# Power_RevA.net
KiCad netlist of a schematic drawn in EAGLE
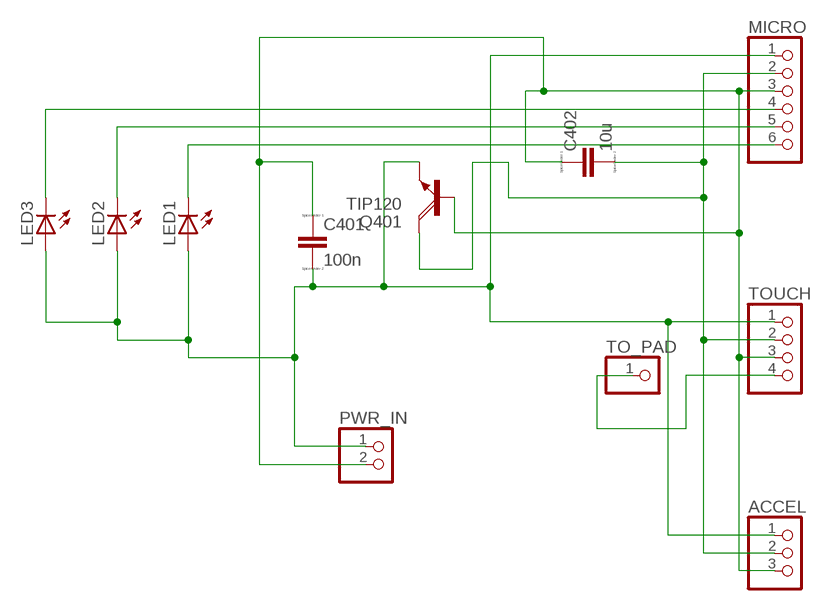
[diagram p0: schematic, sheet 1]

(export (version "E")
  (design (tool "Eeschema 10.0.6"))
  (components
    (comp (ref "ACCEL")
      (value "PINHD-1X3")
      (footprint "eagle-import:1X03")
      (libsource (lib "eagle-import") (part "PINHD-1X3"))
    )
    (comp (ref "C401")
      (value "100n")
      (footprint "eagle-import:C0603")
      (libsource (lib "eagle-import") (part "CC0603"))
    )
    (comp (ref "C402")
      (value "10u")
      (footprint "eagle-import:C0603")
      (libsource (lib "eagle-import") (part "CC0603"))
    )
    (comp (ref "LED1")
      (value "LEDP-LCC-4")
      (footprint "eagle-import:P-LCC-4")
      (libsource (lib "eagle-import") (part "LEDP-LCC-4"))
    )
    (comp (ref "LED2")
      (value "LEDP-LCC-4")
      (footprint "eagle-import:P-LCC-4")
      (libsource (lib "eagle-import") (part "LEDP-LCC-4"))
    )
    (comp (ref "LED3")
      (value "LEDP-LCC-4")
      (footprint "eagle-import:P-LCC-4")
      (libsource (lib "eagle-import") (part "LEDP-LCC-4"))
    )
    (comp (ref "MICRO")
      (value "PINHD-1X6")
      (footprint "eagle-import:1X06")
      (libsource (lib "eagle-import") (part "PINHD-1X6"))
    )
    (comp (ref "PWR_IN")
      (value "PINHD-1X2")
      (footprint "eagle-import:1X02")
      (libsource (lib "eagle-import") (part "PINHD-1X2"))
    )
    (comp (ref "Q401")
      (value "TIP120")
      (footprint "eagle-import:TO220AH")
      (libsource (lib "eagle-import") (part "TIP120"))
    )
    (comp (ref "TOUCH")
      (value "PINHD-1X4")
      (footprint "eagle-import:1X04")
      (libsource (lib "eagle-import") (part "PINHD-1X4"))
    )
    (comp (ref "TO_PAD")
      (value "PINHD-1X1")
      (footprint "eagle-import:1X01")
      (libsource (lib "eagle-import") (part "PINHD-1X1"))
    )
  )
  (nets
    (net (code "1") (name "Net-(ACCEL-Pad1)") (class "Default")
      (node (ref "ACCEL") (pin "1") (pinfunction "1_1") (pintype "passive"))
      (node (ref "C401") (pin "2") (pinfunction "2_2") (pintype "passive"))
      (node (ref "LED1") (pin "A") (pinfunction "A_A") (pintype "passive"))
      (node (ref "LED2") (pin "A") (pinfunction "A_A") (pintype "passive"))
      (node (ref "LED3") (pin "A") (pinfunction "A_A") (pintype "passive"))
      (node (ref "MICRO") (pin "1") (pinfunction "1_1") (pintype "passive"))
      (node (ref "PWR_IN") (pin "1") (pinfunction "1_1") (pintype "passive"))
      (node (ref "Q401") (pin "E") (pinfunction "E_E") (pintype "passive"))
      (node (ref "TOUCH") (pin "1") (pinfunction "1_1") (pintype "passive"))
    )
    (net (code "2") (name "Net-(ACCEL-Pad2)") (class "Default")
      (node (ref "ACCEL") (pin "2") (pinfunction "2_2") (pintype "passive"))
      (node (ref "C402") (pin "2") (pinfunction "2_2") (pintype "passive"))
      (node (ref "MICRO") (pin "2") (pinfunction "2_2") (pintype "passive"))
      (node (ref "Q401") (pin "C") (pinfunction "C_C") (pintype "passive"))
      (node (ref "TOUCH") (pin "2") (pinfunction "2_2") (pintype "passive"))
    )
    (net (code "3") (name "Net-(ACCEL-Pad3)") (class "Default")
      (node (ref "ACCEL") (pin "3") (pinfunction "3_3") (pintype "passive"))
      (node (ref "C401") (pin "1") (pinfunction "1_1") (pintype "passive"))
      (node (ref "C402") (pin "1") (pinfunction "1_1") (pintype "passive"))
      (node (ref "MICRO") (pin "3") (pinfunction "3_3") (pintype "passive"))
      (node (ref "PWR_IN") (pin "2") (pinfunction "2_2") (pintype "passive"))
      (node (ref "Q401") (pin "B") (pinfunction "B_B") (pintype "passive"))
      (node (ref "TOUCH") (pin "3") (pinfunction "3_3") (pintype "passive"))
    )
    (net (code "4") (name "Net-(LED1-C)") (class "Default")
      (node (ref "LED1") (pin "C@4") (pinfunction "C_C@4") (pintype "passive"))
      (node (ref "MICRO") (pin "6") (pinfunction "6_6") (pintype "passive"))
    )
    (net (code "5") (name "Net-(LED2-C)") (class "Default")
      (node (ref "LED2") (pin "C@4") (pinfunction "C_C@4") (pintype "passive"))
      (node (ref "MICRO") (pin "5") (pinfunction "5_5") (pintype "passive"))
    )
    (net (code "6") (name "Net-(LED3-C)") (class "Default")
      (node (ref "LED3") (pin "C@4") (pinfunction "C_C@4") (pintype "passive"))
      (node (ref "MICRO") (pin "4") (pinfunction "4_4") (pintype "passive"))
    )
    (net (code "7") (name "Net-(TOUCH-Pad4)") (class "Default")
      (node (ref "TOUCH") (pin "4") (pinfunction "4_4") (pintype "passive"))
      (node (ref "TO_PAD") (pin "1") (pinfunction "1_1") (pintype "passive"))
    )
  )
)
